# LED.net
KiCad netlist of a schematic drawn in Altium Designer
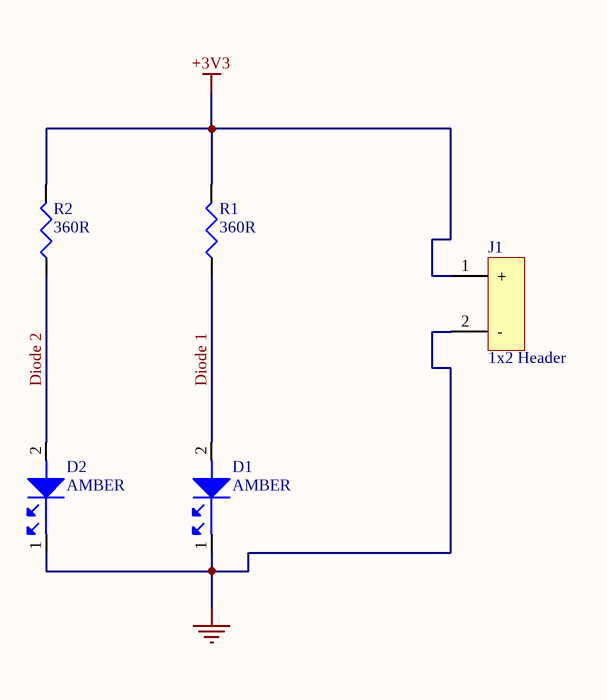
[diagram p0: LED.SchDoc]

(export (version "E")
  (design (tool "Eeschema 10.0.6"))
  (components
    (comp (ref "D1")
      (value "AMBER")
      (footprint "LED0603A")
      (description "LED AMBER ESS II SMD")
      (fields
        (field (name "MANUFACTURER") "Panasonic SSG")
        (field (name "MANUFACTURER PART NUMBER") "LNJ437W84RA")
      )
      (libsource (lib "LED") (part "LNJ437W84RA"))
    )
    (comp (ref "D2")
      (value "AMBER")
      (footprint "LED0603A")
      (description "LED AMBER ESS II SMD")
      (fields
        (field (name "MANUFACTURER") "Panasonic SSG")
        (field (name "MANUFACTURER PART NUMBER") "LNJ437W84RA")
      )
      (libsource (lib "LED") (part "LNJ437W84RA"))
    )
    (comp (ref "J1")
      (value "1x2 Header")
      (footprint "HDR1x2")
      (description "Headers & Wire Housings 2 PIN F/LK HEADER")
      (fields (field (name "MANUFACTURER") "Molex") (field (name "MANUFACTURER PART NUMBER") "22-29-2021"))
      (libsource (lib "LED") (part "22-29-2021 (2)"))
    )
    (comp (ref "R1")
      (value "360R")
      (footprint "R0805")
      (description "RES SMD 360 OHM 1% 1/8W 0805")
      (fields
        (field (name "MANUFACTURER") "Vishay")
        (field (name "MANUFACTURER PART NUMBER") "CRCW0805360RFKEA")
      )
      (libsource (lib "LED") (part "CRCW0805360RFKEA"))
    )
    (comp (ref "R2")
      (value "360R")
      (footprint "R0805")
      (description "RES SMD 360 OHM 1% 1/8W 0805")
      (fields
        (field (name "MANUFACTURER") "Vishay")
        (field (name "MANUFACTURER PART NUMBER") "CRCW0805360RFKEA")
      )
      (libsource (lib "LED") (part "CRCW0805360RFKEA"))
    )
  )
  (nets
    (net (code "1") (name "+3V3") (class "Default")
      (node (ref "J1") (pin "1") (pinfunction "+_1") (pintype "passive"))
      (node (ref "R1") (pin "2") (pinfunction "2_2") (pintype "passive"))
      (node (ref "R2") (pin "2") (pinfunction "2_2") (pintype "passive"))
    )
    (net (code "2") (name "/Diode 1") (class "Default")
      (node (ref "D1") (pin "2") (pinfunction "2_2") (pintype "passive"))
      (node (ref "R1") (pin "1") (pinfunction "1_1") (pintype "passive"))
    )
    (net (code "3") (name "/Diode 2") (class "Default")
      (node (ref "D2") (pin "2") (pinfunction "2_2") (pintype "passive"))
      (node (ref "R2") (pin "1") (pinfunction "1_1") (pintype "passive"))
    )
    (net (code "4") (name "Ground") (class "Default")
      (node (ref "D1") (pin "1") (pinfunction "1_1") (pintype "passive"))
      (node (ref "D2") (pin "1") (pinfunction "1_1") (pintype "passive"))
      (node (ref "J1") (pin "2") (pinfunction "-_2") (pintype "passive"))
    )
  )
)
